# POWER.net
KiCad netlist of a schematic drawn in Altium Designer
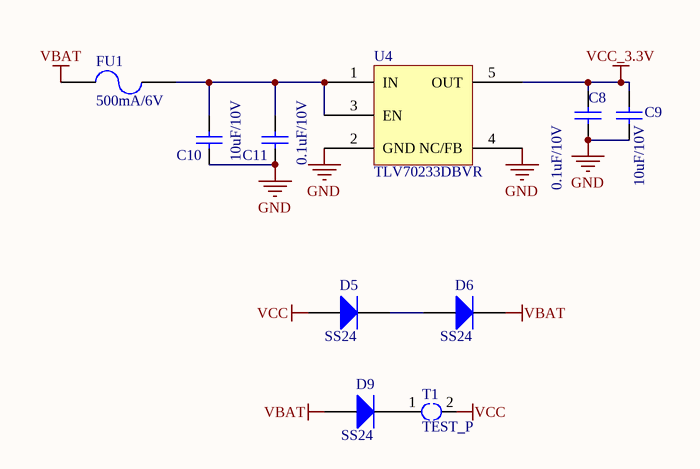
[diagram p0: POWER.SchDoc]

(export (version "E")
  (design (tool "Eeschema 10.0.6"))
  (components
    (comp (ref "C8")
      (value "0.1uF/10V")
      (footprint "0402C")
      (description "Capacitor")
      (fields (field (name "PUBLISHER") "Altium Limited"))
      (libsource (lib "Miscellaneous Devices") (part "Cap"))
    )
    (comp (ref "C9")
      (value "10uF/10V")
      (footprint "0603C")
      (description "Capacitor")
      (fields (field (name "PUBLISHER") "Altium Limited"))
      (libsource (lib "Miscellaneous Devices") (part "Cap"))
    )
    (comp (ref "C10")
      (value "10uF/10V")
      (footprint "0603C")
      (description "Capacitor")
      (fields (field (name "PUBLISHER") "Altium Limited"))
      (libsource (lib "Miscellaneous Devices") (part "Cap"))
    )
    (comp (ref "C11")
      (value "0.1uF/10V")
      (footprint "0402C")
      (description "Capacitor")
      (fields (field (name "PUBLISHER") "Altium Limited"))
      (libsource (lib "Miscellaneous Devices") (part "Cap"))
    )
    (comp (ref "D5")
      (value "SS24")
      (footprint "SMA")
      (description "High Conductance Fast Diode")
      (fields (field (name "PUBLISHER") "Altium Limited"))
      (libsource (lib "Miscellaneous Devices") (part "Diode 1N4148"))
    )
    (comp (ref "D6")
      (value "SS24")
      (footprint "SMA")
      (description "High Conductance Fast Diode")
      (fields (field (name "PUBLISHER") "Altium Limited"))
      (libsource (lib "Miscellaneous Devices") (part "Diode 1N4148"))
    )
    (comp (ref "D9")
      (value "SS24")
      (footprint "SMA")
      (description "High Conductance Fast Diode")
      (fields (field (name "PUBLISHER") "Altium Limited"))
      (libsource (lib "Miscellaneous Devices") (part "Diode 1N4148"))
    )
    (comp (ref "FU1")
      (value "500mA/6V")
      (footprint "0805R")
      (description "Fuse")
      (libsource (lib "SM") (part "FUSE2"))
    )
    (comp (ref "T1")
      (value "TEST_P")
      (footprint "TP_High PWR")
      (libsource (lib "Schlib_20110825") (part "TEST_P"))
    )
    (comp (ref "U4")
      (value "TLV70233DBVR")
      (footprint "SOT23-5(DBV)")
      (libsource (lib "Schlib_20110825") (part "TLV70230DBVR"))
    )
  )
  (nets
    (net (code "1") (name "GND") (class "Default")
      (node (ref "C10") (pin "1") (pinfunction "1_1") (pintype "passive"))
      (node (ref "C11") (pin "2") (pinfunction "2_2") (pintype "passive"))
      (node (ref "C8") (pin "2") (pinfunction "2_2") (pintype "passive"))
      (node (ref "C9") (pin "1") (pinfunction "1_1") (pintype "passive"))
      (node (ref "U4") (pin "2") (pinfunction "GND_2") (pintype "passive"))
      (node (ref "U4") (pin "4") (pinfunction "NC/FB_4") (pintype "passive"))
    )
    (net (code "2") (name "Net-(D5-K)") (class "Default")
      (node (ref "D5") (pin "2") (pinfunction "K_2") (pintype "passive"))
      (node (ref "D6") (pin "1") (pinfunction "A_1") (pintype "passive"))
    )
    (net (code "3") (name "Net-(D9-K)") (class "Default")
      (node (ref "D9") (pin "2") (pinfunction "K_2") (pintype "passive"))
      (node (ref "T1") (pin "1") (pinfunction "1_1") (pintype "passive"))
    )
    (net (code "4") (name "Net-(U4-EN)") (class "Default")
      (node (ref "C10") (pin "2") (pinfunction "2_2") (pintype "passive"))
      (node (ref "C11") (pin "1") (pinfunction "1_1") (pintype "passive"))
      (node (ref "FU1") (pin "2") (pinfunction "2_2") (pintype "passive"))
      (node (ref "U4") (pin "1") (pinfunction "IN_1") (pintype "passive"))
      (node (ref "U4") (pin "3") (pinfunction "EN_3") (pintype "passive"))
    )
    (net (code "5") (name "VBAT") (class "Default")
      (node (ref "D6") (pin "2") (pinfunction "K_2") (pintype "passive"))
      (node (ref "D9") (pin "1") (pinfunction "A_1") (pintype "passive"))
      (node (ref "FU1") (pin "1") (pinfunction "1_1") (pintype "passive"))
    )
    (net (code "6") (name "VCC") (class "Default")
      (node (ref "D5") (pin "1") (pinfunction "A_1") (pintype "passive"))
      (node (ref "T1") (pin "2") (pinfunction "2_2") (pintype "passive"))
    )
    (net (code "7") (name "VCC_3.3V") (class "Default")
      (node (ref "C8") (pin "1") (pinfunction "1_1") (pintype "passive"))
      (node (ref "C9") (pin "2") (pinfunction "2_2") (pintype "passive"))
      (node (ref "U4") (pin "5") (pinfunction "OUT_5") (pintype "passive"))
    )
  )
)
